# V0p2_Main_PCB2.net
KiCad netlist of a schematic drawn in EAGLE
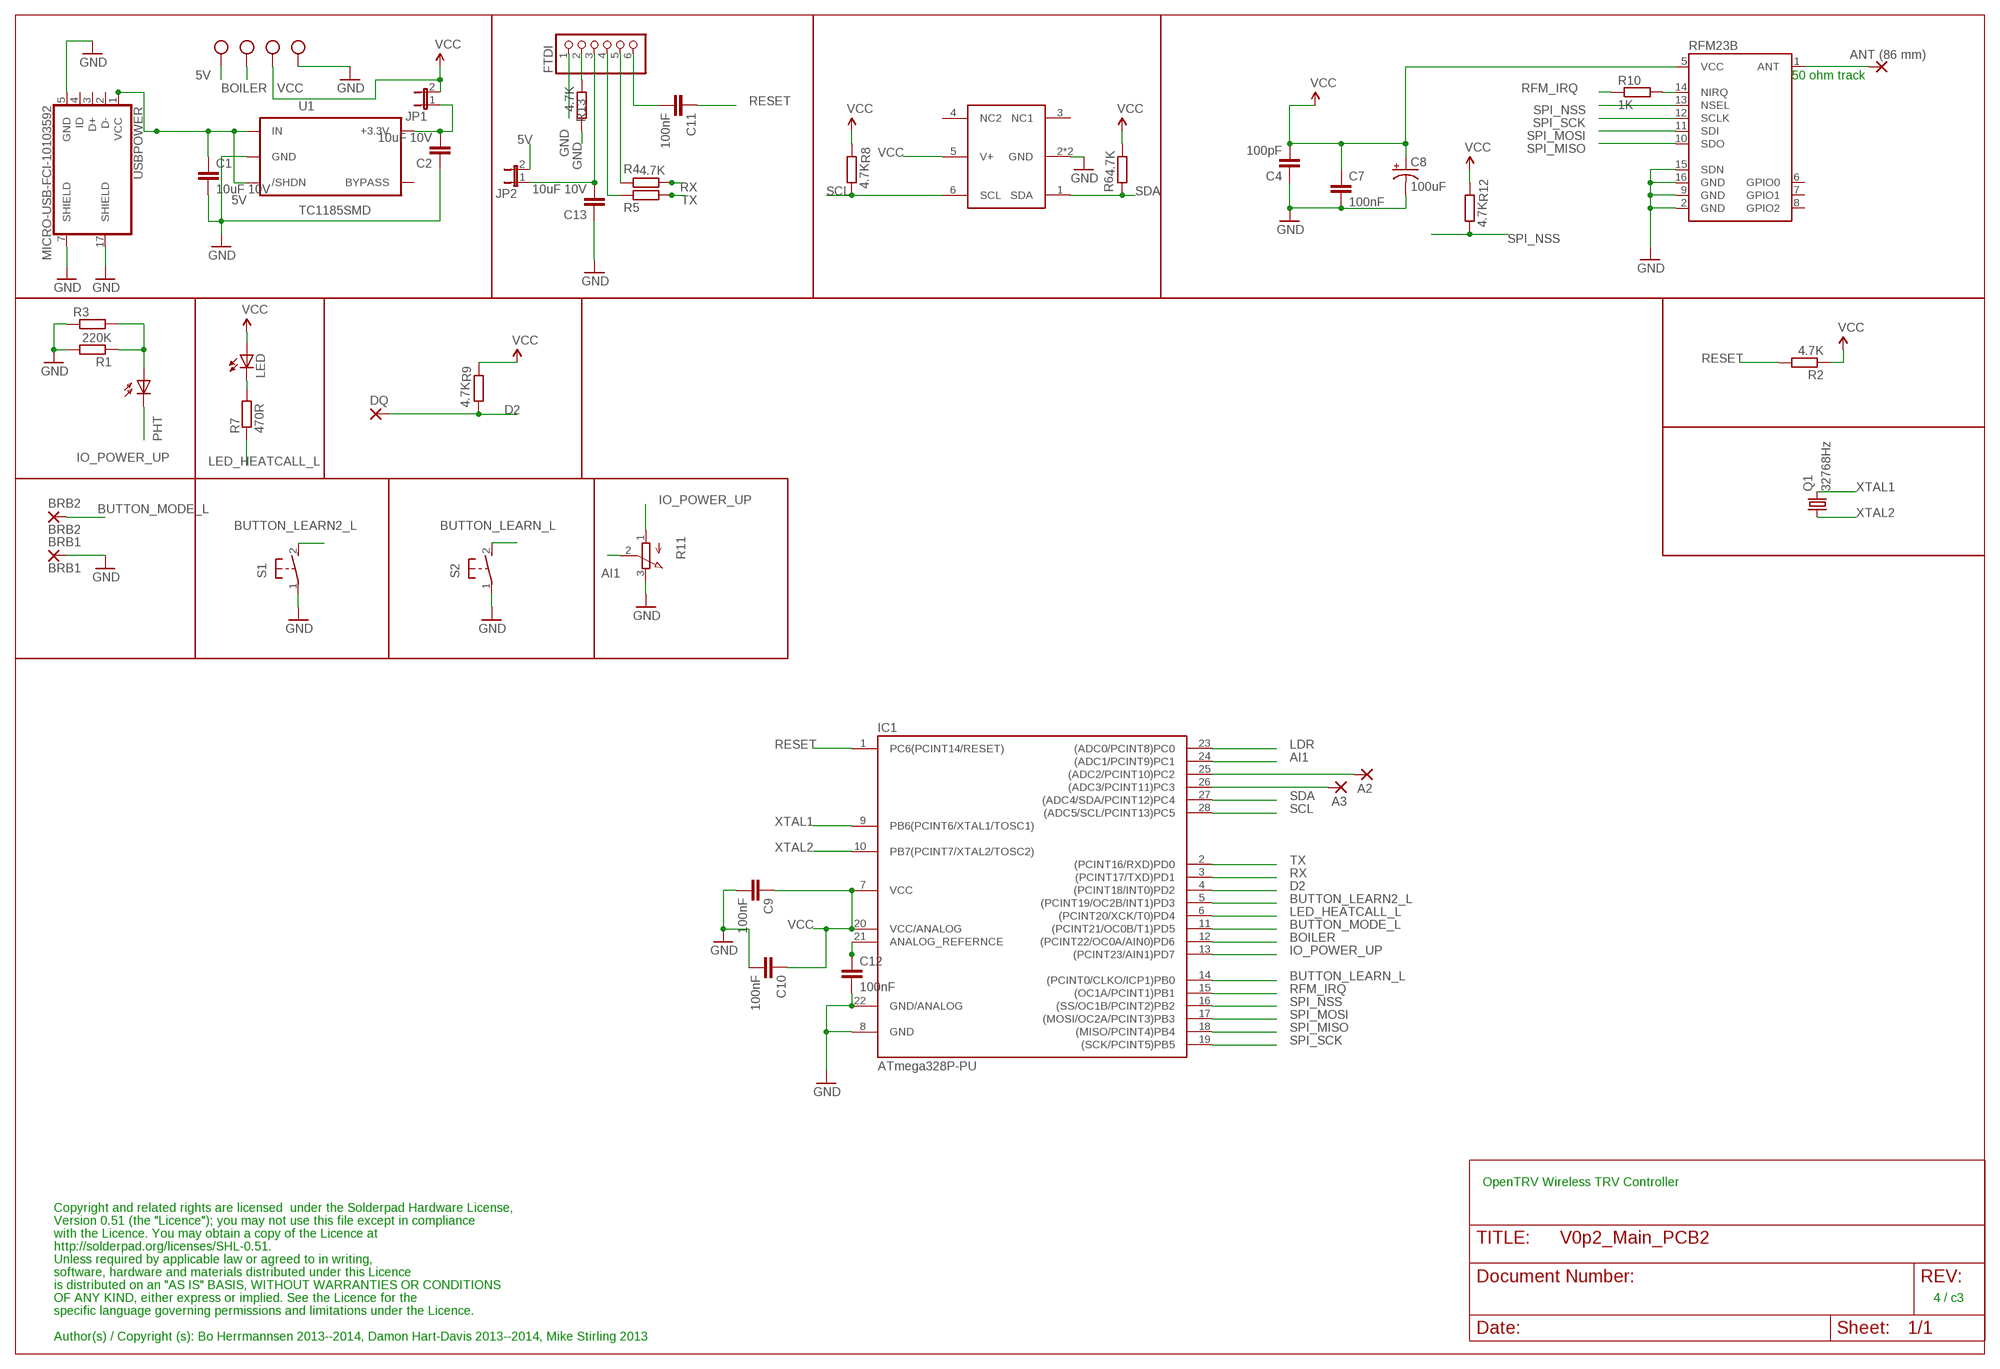
[diagram p0: schematic, sheet 1]

(export (version "E")
  (design (tool "Eeschema 10.0.6"))
  (components
    (comp (ref "A2")
      (value "2,15/1,0")
      (footprint "eagle-import:2,15_1,0")
      (libsource (lib "eagle-import") (part "2,15/1,0"))
    )
    (comp (ref "A3")
      (value "2,15/1,0")
      (footprint "eagle-import:2,15_1,0")
      (libsource (lib "eagle-import") (part "2,15/1,0"))
    )
    (comp (ref "ANT1")
      (value "ANT (86 mm)")
      (footprint "eagle-import:2,15_1,0")
      (libsource (lib "eagle-import") (part "2,15/1,0"))
    )
    (comp (ref "BRB1")
      (value "BRB1")
      (footprint "eagle-import:2,15_1,0")
      (libsource (lib "eagle-import") (part "2,15/1,0"))
    )
    (comp (ref "BRB2")
      (value "BRB2")
      (footprint "eagle-import:2,15_1,0")
      (libsource (lib "eagle-import") (part "2,15/1,0"))
    )
    (comp (ref "C1")
      (value "10uF 10V")
      (footprint "eagle-import:C0603")
      (libsource (lib "eagle-import") (part "C-EUC0603"))
    )
    (comp (ref "C2")
      (value "10uF 10V")
      (footprint "eagle-import:C0603")
      (libsource (lib "eagle-import") (part "C-EUC0603"))
    )
    (comp (ref "C4")
      (value "100pF")
      (footprint "eagle-import:C0603")
      (libsource (lib "eagle-import") (part "C-EUC0603"))
    )
    (comp (ref "C7")
      (value "100nF")
      (footprint "eagle-import:C0603")
      (libsource (lib "eagle-import") (part "C-EUC0603"))
    )
    (comp (ref "C8")
      (value "100uF")
      (footprint "eagle-import:EIA3216")
      (libsource (lib "eagle-import") (part "CAP_POL1206"))
    )
    (comp (ref "C9")
      (value "100nF")
      (footprint "eagle-import:C0603")
      (libsource (lib "eagle-import") (part "C-EUC0603"))
    )
    (comp (ref "C10")
      (value "100nF")
      (footprint "eagle-import:C0603")
      (libsource (lib "eagle-import") (part "C-EUC0603"))
    )
    (comp (ref "C11")
      (value "100nF")
      (footprint "eagle-import:C0603")
      (libsource (lib "eagle-import") (part "C-EUC0603"))
    )
    (comp (ref "C12")
      (value "100nF")
      (footprint "eagle-import:C0603")
      (libsource (lib "eagle-import") (part "C-EUC0603"))
    )
    (comp (ref "C13")
      (value "10uF 10V")
      (footprint "eagle-import:C0603")
      (libsource (lib "eagle-import") (part "C-EUC0603"))
    )
    (comp (ref "DQ")
      (value "2,15/1,0")
      (footprint "eagle-import:2,15_1,0")
      (libsource (lib "eagle-import") (part "2,15/1,0"))
    )
    (comp (ref "FTDI")
      (value "PINHD-1X6/90")
      (footprint "eagle-import:1X06_90")
      (libsource (lib "eagle-import") (part "PINHD-1X6/90"))
    )
    (comp (ref "IC1")
      (value "ATmega328P-PU")
      (footprint "eagle-import:DIL28-3")
      (libsource (lib "eagle-import") (part "ATMEGA168-PU"))
    )
    (comp (ref "JP1")
      (value "JP1E")
      (footprint "eagle-import:JP1")
      (libsource (lib "eagle-import") (part "JP1E"))
    )
    (comp (ref "JP2")
      (value "JP1E")
      (footprint "eagle-import:JP1")
      (libsource (lib "eagle-import") (part "JP1E"))
    )
    (comp (ref "LED")
      (value "LED3MM")
      (footprint "eagle-import:LED3MM")
      (libsource (lib "eagle-import") (part "LED3MM"))
    )
    (comp (ref "PHT")
      (value "BPX65")
      (footprint "eagle-import:BPX65")
      (fields (field (name "MPN") "BPX65."))
      (libsource (lib "eagle-import") (part "BPX65"))
    )
    (comp (ref "Q1")
      (value "32768Hz")
      (footprint "eagle-import:MC-306")
      (fields (field (name "MPN") "MC-306 60.0KHZ  100PPM ,12.5PF"))
      (libsource (lib "eagle-import") (part "MC-306"))
    )
    (comp (ref "R1")
      (value "220K")
      (footprint "eagle-import:R0603")
      (libsource (lib "eagle-import") (part "R-EU_R0603"))
    )
    (comp (ref "R2")
      (value "4.7K")
      (footprint "eagle-import:R0603")
      (libsource (lib "eagle-import") (part "R-EU_R0603"))
    )
    (comp (ref "R3")
      (value "R-EU_0309/V")
      (footprint "eagle-import:0309V")
      (libsource (lib "eagle-import") (part "R-EU_0309/V"))
    )
    (comp (ref "R4")
      (value "4.7K")
      (footprint "eagle-import:R0603")
      (libsource (lib "eagle-import") (part "R-EU_R0603"))
    )
    (comp (ref "R5")
      (value "4.7K")
      (footprint "eagle-import:R0603")
      (libsource (lib "eagle-import") (part "R-EU_R0603"))
    )
    (comp (ref "R6")
      (value "4.7K")
      (footprint "eagle-import:R0603")
      (libsource (lib "eagle-import") (part "R-EU_R0603"))
    )
    (comp (ref "R7")
      (value "470R")
      (footprint "eagle-import:R0603")
      (libsource (lib "eagle-import") (part "R-EU_R0603"))
    )
    (comp (ref "R8")
      (value "4.7K")
      (footprint "eagle-import:R0603")
      (libsource (lib "eagle-import") (part "R-EU_R0603"))
    )
    (comp (ref "R9")
      (value "4.7K")
      (footprint "eagle-import:R0603")
      (libsource (lib "eagle-import") (part "R-EU_R0603"))
    )
    (comp (ref "R10")
      (value "1K")
      (footprint "eagle-import:R0603")
      (libsource (lib "eagle-import") (part "R-EU_R0603"))
    )
    (comp (ref "R11")
      (value "EVUE2A")
      (footprint "eagle-import:EVUE")
      (libsource (lib "eagle-import") (part "EVUE2A"))
    )
    (comp (ref "R12")
      (value "4.7K")
      (footprint "eagle-import:R0603")
      (libsource (lib "eagle-import") (part "R-EU_R0603"))
    )
    (comp (ref "R13")
      (value "4.7K")
      (footprint "eagle-import:R0603")
      (libsource (lib "eagle-import") (part "R-EU_R0603"))
    )
    (comp (ref "RFM23B")
      (value "RFM23B")
      (footprint "eagle-import:RFM23-XXX-S1")
      (libsource (lib "eagle-import") (part "RFM23B"))
    )
    (comp (ref "S1")
      (value "31-XX")
      (footprint "eagle-import:B3F-31XX")
      (libsource (lib "eagle-import") (part "31-XX"))
    )
    (comp (ref "S2")
      (value "31-XX")
      (footprint "eagle-import:B3F-31XX")
      (libsource (lib "eagle-import") (part "31-XX"))
    )
    (comp (ref "U$4")
      (value "SHT21")
      (footprint "eagle-import:SHT21")
      (libsource (lib "eagle-import") (part "SHT21"))
    )
    (comp (ref "U1")
      (value "TC1185SMD")
      (footprint "eagle-import:TC1185")
      (libsource (lib "eagle-import") (part "TC1185SMD"))
    )
    (comp (ref "USBPOWER")
      (value "MICRO-USB-FCI-10103592")
      (footprint "eagle-import:MICRO-USB-FCI-10103592")
      (libsource (lib "eagle-import") (part "MICRO-USB-FCI-10103592"))
    )
    (comp (ref "X1")
      (value "W237-102")
      (footprint "eagle-import:SCREWTERMINAL")
      (fields (field (name "MPN") "237-102"))
      (libsource (lib "eagle-import") (part "W237-102"))
    )
    (comp (ref "X2")
      (value "W237-102")
      (footprint "eagle-import:SCREWTERMINAL")
      (fields (field (name "MPN") "237-102"))
      (libsource (lib "eagle-import") (part "W237-102"))
    )
  )
  (nets
    (net (code "1") (name "/5V") (class "Default")
      (node (ref "C1") (pin "1") (pinfunction "1_1") (pintype "passive"))
      (node (ref "JP2") (pin "2") (pinfunction "2_2") (pintype "passive"))
      (node (ref "U1") (pin "1") (pinfunction "IN_1") (pintype "passive"))
      (node (ref "U1") (pin "3") (pinfunction "/SHDN_3") (pintype "passive"))
      (node (ref "USBPOWER") (pin "1") (pinfunction "VCC_1") (pintype "bidirectional"))
      (node (ref "X1") (pin "2") (pinfunction "KL_2") (pintype "passive"))
    )
    (net (code "2") (name "/AI1") (class "Default")
      (node (ref "IC1") (pin "24") (pinfunction "(ADC1/PCINT9)PC1_24") (pintype "bidirectional"))
      (node (ref "R11") (pin "2") (pinfunction "S_2") (pintype "passive"))
    )
    (net (code "3") (name "/BOILER") (class "Default")
      (node (ref "IC1") (pin "12") (pinfunction "(PCINT22/OC0A/AIN0)PD6_12") (pintype "bidirectional"))
      (node (ref "X1") (pin "1") (pinfunction "KL_1") (pintype "passive"))
    )
    (net (code "4") (name "/BUTTON_LEARN2_L") (class "Default")
      (node (ref "IC1") (pin "5") (pinfunction "(PCINT19/OC2B/INT1)PD3_5") (pintype "bidirectional"))
      (node (ref "S1") (pin "2") (pinfunction "S_2") (pintype "passive"))
    )
    (net (code "5") (name "/BUTTON_LEARN_L") (class "Default")
      (node (ref "IC1") (pin "14") (pinfunction "(PCINT0/CLKO/ICP1)PB0_14") (pintype "bidirectional"))
      (node (ref "S2") (pin "2") (pinfunction "S_2") (pintype "passive"))
    )
    (net (code "6") (name "/BUTTON_MODE_L") (class "Default")
      (node (ref "BRB2") (pin "1") (pinfunction "P_1") (pintype "passive"))
      (node (ref "IC1") (pin "11") (pinfunction "(PCINT21/OC0B/T1)PD5_11") (pintype "bidirectional"))
    )
    (net (code "7") (name "/D2") (class "Default")
      (node (ref "DQ") (pin "1") (pinfunction "P_1") (pintype "passive"))
      (node (ref "IC1") (pin "4") (pinfunction "(PCINT18/INT0)PD2_4") (pintype "bidirectional"))
      (node (ref "R9") (pin "1") (pinfunction "1_1") (pintype "passive"))
    )
    (net (code "8") (name "/IO_POWER_UP") (class "Default")
      (node (ref "IC1") (pin "13") (pinfunction "(PCINT23/AIN1)PD7_13") (pintype "bidirectional"))
      (node (ref "PHT") (pin "K") (pinfunction "C_K") (pintype "passive"))
      (node (ref "R11") (pin "1") (pinfunction "A_1") (pintype "passive"))
    )
    (net (code "9") (name "/LDR") (class "Default")
      (node (ref "IC1") (pin "23") (pinfunction "(ADC0/PCINT8)PC0_23") (pintype "bidirectional"))
      (node (ref "PHT") (pin "A") (pinfunction "A_A") (pintype "passive"))
      (node (ref "R1") (pin "1") (pinfunction "1_1") (pintype "passive"))
      (node (ref "R3") (pin "2") (pinfunction "2_2") (pintype "passive"))
    )
    (net (code "10") (name "/LED_HEATCALL_L") (class "Default")
      (node (ref "IC1") (pin "6") (pinfunction "(PCINT20/XCK/T0)PD4_6") (pintype "bidirectional"))
      (node (ref "R7") (pin "1") (pinfunction "1_1") (pintype "passive"))
    )
    (net (code "11") (name "/RESET") (class "Default")
      (node (ref "C11") (pin "1") (pinfunction "1_1") (pintype "passive"))
      (node (ref "IC1") (pin "1") (pinfunction "PC6(PCINT14/RESET)_1") (pintype "bidirectional"))
      (node (ref "R2") (pin "2") (pinfunction "2_2") (pintype "passive"))
    )
    (net (code "12") (name "/RFM_IRQ") (class "Default")
      (node (ref "IC1") (pin "15") (pinfunction "(OC1A/PCINT1)PB1_15") (pintype "bidirectional"))
      (node (ref "R10") (pin "1") (pinfunction "1_1") (pintype "passive"))
    )
    (net (code "13") (name "/RX") (class "Default")
      (node (ref "IC1") (pin "3") (pinfunction "(PCINT17/TXD)PD1_3") (pintype "bidirectional"))
      (node (ref "R4") (pin "1") (pinfunction "1_1") (pintype "passive"))
    )
    (net (code "14") (name "/SCL") (class "Default")
      (node (ref "IC1") (pin "28") (pinfunction "(ADC5/SCL/PCINT13)PC5_28") (pintype "bidirectional"))
      (node (ref "R8") (pin "1") (pinfunction "1_1") (pintype "passive"))
      (node (ref "U$4") (pin "6") (pinfunction "SCL_6") (pintype "bidirectional"))
    )
    (net (code "15") (name "/SDA") (class "Default")
      (node (ref "IC1") (pin "27") (pinfunction "(ADC4/SDA/PCINT12)PC4_27") (pintype "bidirectional"))
      (node (ref "R6") (pin "2") (pinfunction "2_2") (pintype "passive"))
      (node (ref "U$4") (pin "1") (pinfunction "SDA_1") (pintype "bidirectional"))
    )
    (net (code "16") (name "/SPI_MISO") (class "Default")
      (node (ref "IC1") (pin "18") (pinfunction "(MISO/PCINT4)PB4_18") (pintype "bidirectional"))
      (node (ref "RFM23B") (pin "10") (pinfunction "SDO_10") (pintype "output"))
    )
    (net (code "17") (name "/SPI_MOSI") (class "Default")
      (node (ref "IC1") (pin "17") (pinfunction "(MOSI/OC2A/PCINT3)PB3_17") (pintype "bidirectional"))
      (node (ref "RFM23B") (pin "11") (pinfunction "SDI_11") (pintype "input"))
    )
    (net (code "18") (name "/SPI_NSS") (class "Default")
      (node (ref "IC1") (pin "16") (pinfunction "(SS/OC1B/PCINT2)PB2_16") (pintype "bidirectional"))
      (node (ref "R12") (pin "1") (pinfunction "1_1") (pintype "passive"))
      (node (ref "RFM23B") (pin "13") (pinfunction "NSEL_13") (pintype "input"))
    )
    (net (code "19") (name "/SPI_SCK") (class "Default")
      (node (ref "IC1") (pin "19") (pinfunction "(SCK/PCINT5)PB5_19") (pintype "bidirectional"))
      (node (ref "RFM23B") (pin "12") (pinfunction "SCLK_12") (pintype "input"))
    )
    (net (code "20") (name "/TX") (class "Default")
      (node (ref "IC1") (pin "2") (pinfunction "(PCINT16/RXD)PD0_2") (pintype "bidirectional"))
      (node (ref "R5") (pin "1") (pinfunction "1_1") (pintype "passive"))
    )
    (net (code "21") (name "/XTAL1") (class "Default")
      (node (ref "IC1") (pin "9") (pinfunction "PB6(PCINT6/XTAL1/TOSC1)_9") (pintype "bidirectional"))
      (node (ref "Q1") (pin "4") (pinfunction "2_4") (pintype "passive"))
    )
    (net (code "22") (name "/XTAL2") (class "Default")
      (node (ref "IC1") (pin "10") (pinfunction "PB7(PCINT7/XTAL2/TOSC2)_10") (pintype "bidirectional"))
      (node (ref "Q1") (pin "1") (pinfunction "1_1") (pintype "passive"))
    )
    (net (code "23") (name "GND") (class "Default")
      (node (ref "BRB1") (pin "1") (pinfunction "P_1") (pintype "passive"))
      (node (ref "C1") (pin "2") (pinfunction "2_2") (pintype "passive"))
      (node (ref "C10") (pin "2") (pinfunction "2_2") (pintype "passive"))
      (node (ref "C12") (pin "2") (pinfunction "2_2") (pintype "passive"))
      (node (ref "C13") (pin "1") (pinfunction "1_1") (pintype "passive"))
      (node (ref "C2") (pin "1") (pinfunction "1_1") (pintype "passive"))
      (node (ref "C4") (pin "1") (pinfunction "1_1") (pintype "passive"))
      (node (ref "C7") (pin "2") (pinfunction "2_2") (pintype "passive"))
      (node (ref "C8") (pin "C") (pinfunction "-_C") (pintype "passive"))
      (node (ref "C9") (pin "2") (pinfunction "2_2") (pintype "passive"))
      (node (ref "FTDI") (pin "1") (pinfunction "1_1") (pintype "passive"))
      (node (ref "IC1") (pin "22") (pinfunction "GND/ANALOG_22") (pintype "power_in"))
      (node (ref "IC1") (pin "8") (pinfunction "GND_8") (pintype "power_in"))
      (node (ref "R1") (pin "2") (pinfunction "2_2") (pintype "passive"))
      (node (ref "R11") (pin "3") (pinfunction "E_3") (pintype "passive"))
      (node (ref "R13") (pin "2") (pinfunction "2_2") (pintype "passive"))
      (node (ref "R3") (pin "1") (pinfunction "1_1") (pintype "passive"))
      (node (ref "RFM23B") (pin "15") (pinfunction "SDN_15") (pintype "input"))
      (node (ref "RFM23B") (pin "16") (pinfunction "GND_16") (pintype "power_in"))
      (node (ref "RFM23B") (pin "2") (pinfunction "GND_2") (pintype "power_in"))
      (node (ref "RFM23B") (pin "9") (pinfunction "GND_9") (pintype "power_in"))
      (node (ref "S1") (pin "1") (pinfunction "P_1") (pintype "passive"))
      (node (ref "S2") (pin "1") (pinfunction "P_1") (pintype "passive"))
      (node (ref "U$4") (pin "2") (pinfunction "GND_2") (pintype "bidirectional"))
      (node (ref "U$4") (pin "P$1") (pinfunction "GND_P$1") (pintype "bidirectional"))
      (node (ref "U1") (pin "2") (pinfunction "GND_2") (pintype "passive"))
      (node (ref "USBPOWER") (pin "17") (pinfunction "SHIELD_17") (pintype "bidirectional"))
      (node (ref "USBPOWER") (pin "5") (pinfunction "GND_5") (pintype "bidirectional"))
      (node (ref "USBPOWER") (pin "7") (pinfunction "SHIELD_7") (pintype "bidirectional"))
      (node (ref "X2") (pin "2") (pinfunction "KL_2") (pintype "passive"))
    )
    (net (code "24") (name "Net-(A2-P)") (class "Default")
      (node (ref "A2") (pin "1") (pinfunction "P_1") (pintype "passive"))
      (node (ref "IC1") (pin "25") (pinfunction "(ADC2/PCINT10)PC2_25") (pintype "bidirectional"))
    )
    (net (code "25") (name "Net-(A3-P)") (class "Default")
      (node (ref "A3") (pin "1") (pinfunction "P_1") (pintype "passive"))
      (node (ref "IC1") (pin "26") (pinfunction "(ADC3/PCINT11)PC3_26") (pintype "bidirectional"))
    )
    (net (code "26") (name "Net-(ANT1-P)") (class "Default")
      (node (ref "ANT1") (pin "1") (pinfunction "P_1") (pintype "passive"))
      (node (ref "RFM23B") (pin "1") (pinfunction "ANT_1") (pintype "bidirectional"))
    )
    (net (code "27") (name "Net-(C11-Pad2)") (class "Default")
      (node (ref "C11") (pin "2") (pinfunction "2_2") (pintype "passive"))
      (node (ref "FTDI") (pin "6") (pinfunction "6_6") (pintype "passive"))
    )
    (net (code "28") (name "Net-(C13-Pad2)") (class "Default")
      (node (ref "C13") (pin "2") (pinfunction "2_2") (pintype "passive"))
      (node (ref "FTDI") (pin "3") (pinfunction "3_3") (pintype "passive"))
      (node (ref "JP2") (pin "1") (pinfunction "1_1") (pintype "passive"))
    )
    (net (code "29") (name "Net-(FTDI-Pad2)") (class "Default")
      (node (ref "FTDI") (pin "2") (pinfunction "2_2") (pintype "passive"))
      (node (ref "R13") (pin "1") (pinfunction "1_1") (pintype "passive"))
    )
    (net (code "30") (name "Net-(FTDI-Pad4)") (class "Default")
      (node (ref "FTDI") (pin "4") (pinfunction "4_4") (pintype "passive"))
      (node (ref "R5") (pin "2") (pinfunction "2_2") (pintype "passive"))
    )
    (net (code "31") (name "Net-(FTDI-Pad5)") (class "Default")
      (node (ref "FTDI") (pin "5") (pinfunction "5_5") (pintype "passive"))
      (node (ref "R4") (pin "2") (pinfunction "2_2") (pintype "passive"))
    )
    (net (code "32") (name "Net-(IC1-ANALOG_REFERNCE)") (class "Default")
      (node (ref "C12") (pin "1") (pinfunction "1_1") (pintype "passive"))
      (node (ref "IC1") (pin "21") (pinfunction "ANALOG_REFERNCE_21") (pintype "passive"))
    )
    (net (code "33") (name "Net-(LED-C)") (class "Default")
      (node (ref "LED") (pin "K") (pinfunction "C_K") (pintype "passive"))
      (node (ref "R7") (pin "2") (pinfunction "2_2") (pintype "passive"))
    )
    (net (code "34") (name "Net-(RFM23B-NIRQ)") (class "Default")
      (node (ref "R10") (pin "2") (pinfunction "2_2") (pintype "passive"))
      (node (ref "RFM23B") (pin "14") (pinfunction "NIRQ_14") (pintype "output"))
    )
    (net (code "35") (name "Net-(U1-+3.3V)") (class "Default")
      (node (ref "C2") (pin "2") (pinfunction "2_2") (pintype "passive"))
      (node (ref "JP1") (pin "1") (pinfunction "1_1") (pintype "passive"))
      (node (ref "U1") (pin "5") (pinfunction "+3.3V_5") (pintype "power_in"))
    )
    (net (code "36") (name "VCC") (class "Default")
      (node (ref "C10") (pin "1") (pinfunction "1_1") (pintype "passive"))
      (node (ref "C4") (pin "2") (pinfunction "2_2") (pintype "passive"))
      (node (ref "C7") (pin "1") (pinfunction "1_1") (pintype "passive"))
      (node (ref "C8") (pin "A") (pinfunction "+_A") (pintype "passive"))
      (node (ref "C9") (pin "1") (pinfunction "1_1") (pintype "passive"))
      (node (ref "IC1") (pin "20") (pinfunction "VCC/ANALOG_20") (pintype "passive"))
      (node (ref "IC1") (pin "7") (pinfunction "VCC_7") (pintype "power_in"))
      (node (ref "JP1") (pin "2") (pinfunction "2_2") (pintype "passive"))
      (node (ref "LED") (pin "A") (pinfunction "A_A") (pintype "passive"))
      (node (ref "R12") (pin "2") (pinfunction "2_2") (pintype "passive"))
      (node (ref "R2") (pin "1") (pinfunction "1_1") (pintype "passive"))
      (node (ref "R6") (pin "1") (pinfunction "1_1") (pintype "passive"))
      (node (ref "R8") (pin "2") (pinfunction "2_2") (pintype "passive"))
      (node (ref "R9") (pin "2") (pinfunction "2_2") (pintype "passive"))
      (node (ref "RFM23B") (pin "5") (pinfunction "VCC_5") (pintype "bidirectional"))
      (node (ref "U$4") (pin "5") (pinfunction "V+_5") (pintype "bidirectional"))
      (node (ref "X2") (pin "1") (pinfunction "KL_1") (pintype "passive"))
    )
    (net (code "37") (name "unconnected-(RFM23B-GPIO0-Pad6)") (class "Default")
      (node (ref "RFM23B") (pin "6") (pinfunction "GPIO0_6") (pintype "bidirectional"))
    )
    (net (code "38") (name "unconnected-(RFM23B-GPIO1-Pad7)") (class "Default")
      (node (ref "RFM23B") (pin "7") (pinfunction "GPIO1_7") (pintype "bidirectional"))
    )
    (net (code "39") (name "unconnected-(RFM23B-GPIO2-Pad8)") (class "Default")
      (node (ref "RFM23B") (pin "8") (pinfunction "GPIO2_8") (pintype "bidirectional"))
    )
    (net (code "40") (name "unconnected-(U$4-NC1-Pad3)") (class "Default")
      (node (ref "U$4") (pin "3") (pinfunction "NC1_3") (pintype "bidirectional"))
    )
    (net (code "41") (name "unconnected-(U$4-NC2-Pad4)") (class "Default")
      (node (ref "U$4") (pin "4") (pinfunction "NC2_4") (pintype "bidirectional"))
    )
    (net (code "42") (name "unconnected-(U1-BYPASS-Pad4)") (class "Default")
      (node (ref "U1") (pin "4") (pinfunction "BYPASS_4") (pintype "passive"))
    )
    (net (code "43") (name "unconnected-(USBPOWER-D+-Pad3)") (class "Default")
      (node (ref "USBPOWER") (pin "3") (pinfunction "D+_3") (pintype "bidirectional"))
    )
    (net (code "44") (name "unconnected-(USBPOWER-D--Pad2)") (class "Default")
      (node (ref "USBPOWER") (pin "2") (pinfunction "D-_2") (pintype "bidirectional"))
    )
    (net (code "45") (name "unconnected-(USBPOWER-ID-Pad4)") (class "Default")
      (node (ref "USBPOWER") (pin "4") (pinfunction "ID_4") (pintype "bidirectional"))
    )
  )
)
